# MCU098_01_MSPM0G3507_Target_Device.net
KiCad netlist of a schematic drawn in Altium Designer
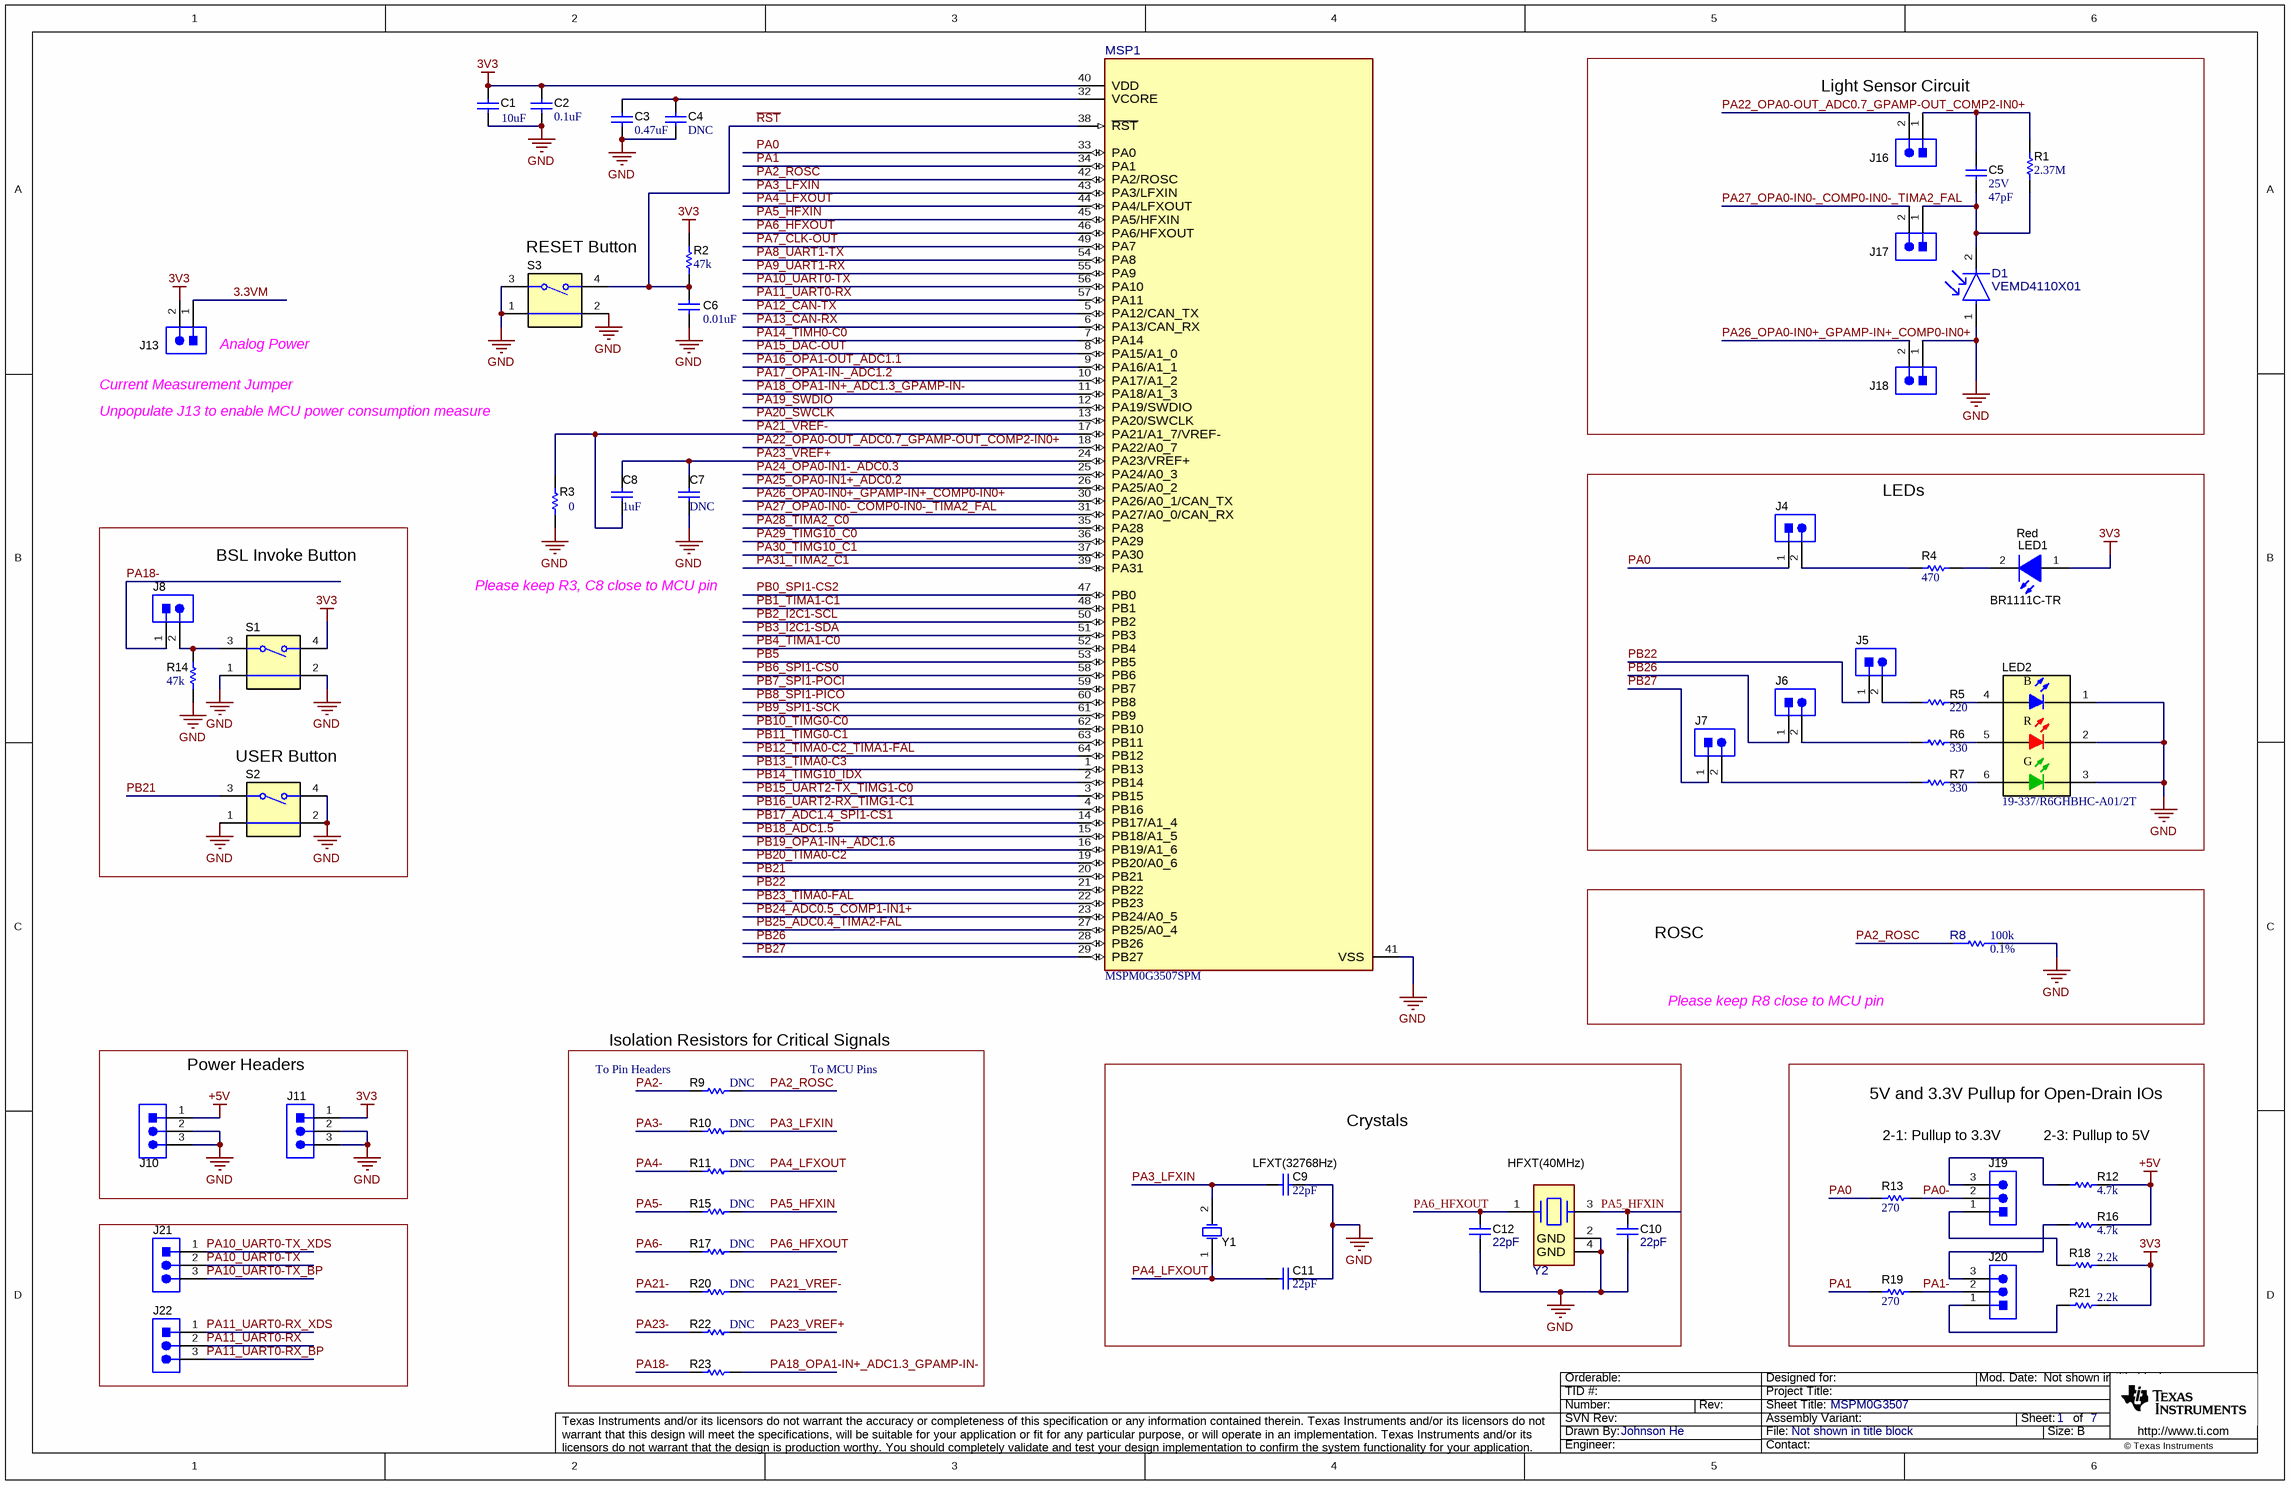
[diagram p0: MCU098_01_MSPM0G3507_Target_Device.SchDoc]

(export (version "E")
  (design (tool "Eeschema 10.0.6"))
  (components
    (comp (ref "C1")
      (value "GRM188R60J106ME84")
      (footprint "0603")
      (description "CAP, CERM, 10 uF, 6.3 V, +/- 20%, X5R, 0603")
      (fields
        (field (name "MANUFACTURER") "MuRata")
        (field (name "VALUEDISPLAYED") "10uF")
        (field (name "PUBLISHER") "Texas Instruments")
      )
      (libsource (lib "Altium Vault - TI") (part "Capacitor"))
    )
    (comp (ref "C2")
      (value "GRM155R61H104ME14D")
      (footprint "0402")
      (description "CAP, CERM, 0.1 uF, 50 V, +/- 20%, X5R, 0402")
      (fields
        (field (name "MANUFACTURER") "MuRata")
        (field (name "VALUEDISPLAYED") "0.1uF")
        (field (name "PUBLISHER") "Texas Instruments")
      )
      (libsource (lib "Altium Vault - TI") (part "Capacitor"))
    )
    (comp (ref "C3")
      (value "GRM155R60J474KE19D")
      (footprint "0402")
      (description "CAP, CERM, 0.47 uF, 6.3 V, +/- 10%, X5R, 0402")
      (fields
        (field (name "MANUFACTURER") "MuRata")
        (field (name "VALUEDISPLAYED") "0.47uF")
        (field (name "PUBLISHER") "Texas Instruments")
      )
      (libsource (lib "Altium Vault - TI") (part "Capacitor"))
    )
    (comp (ref "C4")
      (value "GRM155R61H104ME14D")
      (footprint "0402")
      (description "CAP, CERM, 0.1 uF, 50 V, +/- 20%, X5R, 0402")
      (fields
        (field (name "MANUFACTURER") "MuRata")
        (field (name "VALUEDISPLAYED") "DNC")
        (field (name "PUBLISHER") "Texas Instruments")
      )
      (libsource (lib "Altium Vault - TI") (part "Capacitor"))
    )
    (comp (ref "C5")
      (value "GRM1555C1E470JA01D")
      (footprint "0402")
      (description "CAP, CERM, 47 pF, 25 V, +/- 5%, C0G/NP0, 0402")
      (fields
        (field (name "MANUFACTURER") "MuRata")
        (field (name "VDC_V") "25V")
        (field (name "VALUEDISPLAYED") "47pF")
        (field (name "PUBLISHER") "Texas Instruments")
      )
      (libsource (lib "Altium Vault - TI") (part "Capacitor"))
    )
    (comp (ref "C6")
      (value "GRM155R61C103KA01D")
      (footprint "0402")
      (description "CAP, CERM, 0.01 uF, 16 V, +/- 10%, X5R, 0402")
      (fields
        (field (name "MANUFACTURER") "MuRata")
        (field (name "VALUEDISPLAYED") "0.01uF")
        (field (name "PUBLISHER") "Texas Instruments")
      )
      (libsource (lib "Altium Vault - TI") (part "Capacitor"))
    )
    (comp (ref "C7")
      (value "C1608X5R1E105K080AC")
      (footprint "0603")
      (description "CAP, CERM, 1 uF, 25 V, +/- 10%, X5R, 0603")
      (fields
        (field (name "MANUFACTURER") "TDK")
        (field (name "VALUEDISPLAYED") "DNC")
        (field (name "PUBLISHER") "Texas Instruments")
      )
      (libsource (lib "Altium Vault - TI") (part "Capacitor"))
    )
    (comp (ref "C8")
      (value "1uF")
      (footprint "0603")
      (description "CAP, CERM, 1 uF, 25 V, +/- 10%, X5R, 0603")
      (fields
        (field (name "MANUFACTURER") "TDK")
        (field (name "PARTNUMBER") "C1608X5R1E105K080AC")
        (field (name "PUBLISHER") "Texas Instruments")
      )
      (libsource (lib "Altium Vault - TI") (part "Capacitor"))
    )
    (comp (ref "C9")
      (value "GRM1555C1H220JA01D")
      (footprint "0402")
      (description "CAP, CERM, 22 pF, 50 V, +/- 5%, C0G/NP0, 0402")
      (fields
        (field (name "MANUFACTURER") "MuRata")
        (field (name "VALUEDISPLAYED") "22pF")
        (field (name "PUBLISHER") "Texas Instruments")
      )
      (libsource (lib "Altium Vault - TI") (part "Capacitor"))
    )
    (comp (ref "C10")
      (value "GRM1555C1H220JA01D")
      (footprint "0402")
      (description "CAP, CERM, 22 pF, 50 V, +/- 5%, C0G/NP0, 0402")
      (fields
        (field (name "MANUFACTURER") "MuRata")
        (field (name "VALUEDISPLAYED") "22pF")
        (field (name "PUBLISHER") "Texas Instruments")
      )
      (libsource (lib "Altium Vault - TI") (part "Capacitor"))
    )
    (comp (ref "C11")
      (value "GRM1555C1H220JA01D")
      (footprint "0402")
      (description "CAP, CERM, 22 pF, 50 V, +/- 5%, C0G/NP0, 0402")
      (fields
        (field (name "MANUFACTURER") "MuRata")
        (field (name "VALUEDISPLAYED") "22pF")
        (field (name "PUBLISHER") "Texas Instruments")
      )
      (libsource (lib "Altium Vault - TI") (part "Capacitor"))
    )
    (comp (ref "C12")
      (value "GRM1555C1H220JA01D")
      (footprint "0402")
      (description "CAP, CERM, 22 pF, 50 V, +/- 5%, C0G/NP0, 0402")
      (fields
        (field (name "MANUFACTURER") "MuRata")
        (field (name "VALUEDISPLAYED") "22pF")
        (field (name "PUBLISHER") "Texas Instruments")
      )
      (libsource (lib "Altium Vault - TI") (part "Capacitor"))
    )
    (comp (ref "D1")
      (value "VEMD4110X01")
      (footprint "FP-VEMD4110X01_0805-MFG")
      (description "Photodiode PIN Chip 910nm Automotive 2-Pin Case 0805(2012Metric) T/R")
      (fields
        (field (name "MANUFACTURER") "Vishay")
        (field (name "DIGIKEY PART NUMBER") "751-VEMD4110X01CT-ND")
      )
      (libsource (lib "Altium Vault - TI") (part "SYM-VEMD4110X01"))
    )
    (comp (ref "J4")
      (value "90120-0122")
      (footprint "CONN_90120-0122")
      (description "Header, 100mil, 2x1, Tin, TH")
      (fields (field (name "MANUFACTURER") "Molex") (field (name "PUBLISHER") "Texas Instruments"))
      (libsource (lib "") (part "Header_2x1_1"))
    )
    (comp (ref "J5")
      (value "90120-0122")
      (footprint "CONN_90120-0122")
      (description "Header, 100mil, 2x1, Tin, TH")
      (fields (field (name "MANUFACTURER") "Molex") (field (name "PUBLISHER") "Texas Instruments"))
      (libsource (lib "") (part "Header_2x1_1"))
    )
    (comp (ref "J6")
      (value "90120-0122")
      (footprint "CONN_90120-0122")
      (description "Header, 100mil, 2x1, Tin, TH")
      (fields (field (name "MANUFACTURER") "Molex") (field (name "PUBLISHER") "Texas Instruments"))
      (libsource (lib "") (part "Header_2x1_1"))
    )
    (comp (ref "J7")
      (value "90120-0122")
      (footprint "CONN_90120-0122")
      (description "Header, 100mil, 2x1, Tin, TH")
      (fields (field (name "MANUFACTURER") "Molex") (field (name "PUBLISHER") "Texas Instruments"))
      (libsource (lib "") (part "Header_2x1_1"))
    )
    (comp (ref "J8")
      (value "90120-0122")
      (footprint "CONN_90120-0122")
      (description "Header, 100mil, 2x1, Tin, TH")
      (fields (field (name "MANUFACTURER") "Molex") (field (name "PUBLISHER") "Texas Instruments"))
      (libsource (lib "") (part "Header_2x1_1"))
    )
    (comp (ref "J10")
      (value "PEC03SAAN")
      (footprint "PEC03SAAN_Launchpad_5V0")
      (description "Header, 100mil, 3x1, Tin, TH")
      (fields
        (field (name "MANUFACTURER") "Sullins Connector Solutions")
        (field (name "PUBLISHER") "Texas Instruments")
      )
      (libsource (lib "") (part "Header_3x1_Launchpad_1"))
    )
    (comp (ref "J11")
      (value "PEC03SAAN")
      (footprint "PEC03SAAN_Launchpad_3V3")
      (description "Header, 100mil, 3x1, Tin, TH")
      (fields
        (field (name "MANUFACTURER") "Sullins Connector Solutions")
        (field (name "PUBLISHER") "Texas Instruments")
      )
      (libsource (lib "") (part "Header_3x1_Launchpad_1"))
    )
    (comp (ref "J13")
      (value "90120-0122")
      (footprint "CONN_90120-0122")
      (description "Header, 100mil, 2x1, Tin, TH")
      (fields (field (name "MANUFACTURER") "Molex") (field (name "PUBLISHER") "Texas Instruments"))
      (libsource (lib "Altium Vault - TI") (part "Header_2x1"))
    )
    (comp (ref "J16")
      (value "90120-0122")
      (footprint "CONN_90120-0122")
      (description "Header, 100mil, 2x1, Tin, TH")
      (fields (field (name "MANUFACTURER") "Molex") (field (name "PUBLISHER") "Texas Instruments"))
      (libsource (lib "Altium Vault - TI") (part "Header_2x1"))
    )
    (comp (ref "J17")
      (value "90120-0122")
      (footprint "CONN_90120-0122")
      (description "Header, 100mil, 2x1, Tin, TH")
      (fields (field (name "MANUFACTURER") "Molex") (field (name "PUBLISHER") "Texas Instruments"))
      (libsource (lib "Altium Vault - TI") (part "Header_2x1"))
    )
    (comp (ref "J18")
      (value "90120-0122")
      (footprint "CONN_90120-0122")
      (description "Header, 100mil, 2x1, Tin, TH")
      (fields (field (name "MANUFACTURER") "Molex") (field (name "PUBLISHER") "Texas Instruments"))
      (libsource (lib "Altium Vault - TI") (part "Header_2x1"))
    )
    (comp (ref "J19")
      (value "PEC03SAAN")
      (footprint "CONN_PEC03SAAN")
      (description "Header, 100mil, 3x1, Tin, TH")
      (fields
        (field (name "MANUFACTURER") "Sullins Connector Solutions")
        (field (name "PUBLISHER") "Texas Instruments")
      )
      (libsource (lib "Altium Vault - TI") (part "Header_3x1_Launchpad"))
    )
    (comp (ref "J20")
      (value "PEC03SAAN")
      (footprint "CONN_PEC03SAAN")
      (description "Header, 100mil, 3x1, Tin, TH")
      (fields
        (field (name "MANUFACTURER") "Sullins Connector Solutions")
        (field (name "PUBLISHER") "Texas Instruments")
      )
      (libsource (lib "Altium Vault - TI") (part "Header_3x1_Launchpad"))
    )
    (comp (ref "J21")
      (value "PEC03SAAN")
      (footprint "CONN_PEC03SAAN")
      (description "Header, 100mil, 3x1, Tin, TH")
      (fields
        (field (name "MANUFACTURER") "Sullins Connector Solutions")
        (field (name "PUBLISHER") "Texas Instruments")
      )
      (libsource (lib "") (part "Header_3x1_Launchpad_1"))
    )
    (comp (ref "J22")
      (value "PEC03SAAN")
      (footprint "CONN_PEC03SAAN")
      (description "Header, 100mil, 3x1, Tin, TH")
      (fields
        (field (name "MANUFACTURER") "Sullins Connector Solutions")
        (field (name "PUBLISHER") "Texas Instruments")
      )
      (libsource (lib "") (part "Header_3x1_Launchpad_1"))
    )
    (comp (ref "LED1")
      (value "BR1111C-TR")
      (footprint "1111C_Red")
      (description "LED, Red, SMD")
      (fields (field (name "ALTIUM_VALUE") "Red") (field (name "MANUFACTURER") "Stanley Electric Co., LTD"))
      (libsource (lib "Altium Vault - TI") (part "LED"))
    )
    (comp (ref "LED2")
      (value "19-337/R6GHBHC-A01/2T")
      (footprint "19-337_RGB")
      (description "LED, RGB, SMD")
      (fields (field (name "MANUFACTURER") "Everlight") (field (name "PUBLISHER") "Texas Instruments"))
      (libsource (lib "Altium Vault - TI") (part "LED_RGB_A456K123"))
    )
    (comp (ref "MSP1")
      (value "MSPM0G3507SPM")
      (footprint "PM0064A-MFG")
      (description "Mixed-Signal Microcontrollers With CAN-FD Interface LQFP64")
      (fields (field (name "PARTNUMBER") "MSPM0G3507SPM") (field (name "MANUFACTURER") "Texas Instruments"))
      (libsource (lib "Altium Vault - TI") (part "SYM-MSPM0G3507SPM"))
    )
    (comp (ref "R1")
      (value "CRCW06032M37FKEA")
      (footprint "0603")
      (description "RES, 2.37 M, 1%, 0.1 W, 0603")
      (fields
        (field (name "MANUFACTURER") "Vishay-Dale")
        (field (name "VALUEDISPLAYED") "2.37M")
        (field (name "PUBLISHER") "Texas Instruments")
      )
      (libsource (lib "Altium Vault - TI") (part "Resistor"))
    )
    (comp (ref "R2")
      (value "CRCW040247K0JNED")
      (footprint "0402")
      (description "RES, 47 k, 5%, 0.063 W, 0402")
      (fields
        (field (name "MANUFACTURER") "Vishay-Dale")
        (field (name "VALUEDISPLAYED") "47k")
        (field (name "PUBLISHER") "Texas Instruments")
      )
      (libsource (lib "Altium Vault - TI") (part "Resistor"))
    )
    (comp (ref "R3")
      (value "0")
      (footprint "0603")
      (description "RES, 0, 5%, 0.1 W, 0603")
      (fields (field (name "MANUFACTURER") "Yageo") (field (name "PARTNUMBER") "RC0603JR-070RL"))
      (libsource (lib "Altium Vault - TI") (part "Resistor"))
    )
    (comp (ref "R4")
      (value "CRCW0402470RJNED")
      (footprint "0402")
      (description "RES, 470, 5%, 0.063 W, 0402")
      (fields
        (field (name "MANUFACTURER") "Vishay-Dale")
        (field (name "VALUEDISPLAYED") "470")
        (field (name "PUBLISHER") "Texas Instruments")
      )
      (libsource (lib "Altium Vault - TI") (part "Resistor"))
    )
    (comp (ref "R5")
      (value "CRCW0402220RJNED")
      (footprint "0402")
      (description "RES, 220, 5%, 0.063 W, 0402")
      (fields
        (field (name "MANUFACTURER") "Vishay-Dale")
        (field (name "VALUEDISPLAYED") "220")
        (field (name "PUBLISHER") "Texas Instruments")
      )
      (libsource (lib "Altium Vault - TI") (part "Resistor"))
    )
    (comp (ref "R6")
      (value "CRCW0402330RJNED")
      (footprint "0402")
      (description "RES, 330, 5%, 0.063 W, 0402")
      (fields
        (field (name "MANUFACTURER") "Vishay-Dale")
        (field (name "VALUEDISPLAYED") "330")
        (field (name "PUBLISHER") "Texas Instruments")
      )
      (libsource (lib "Altium Vault - TI") (part "Resistor"))
    )
    (comp (ref "R7")
      (value "CRCW0402330RJNED")
      (footprint "0402")
      (description "RES, 330, 5%, 0.063 W, 0402")
      (fields
        (field (name "MANUFACTURER") "Vishay-Dale")
        (field (name "VALUEDISPLAYED") "330")
        (field (name "PUBLISHER") "Texas Instruments")
      )
      (libsource (lib "Altium Vault - TI") (part "Resistor"))
    )
    (comp (ref "R8")
      (value "ERA-2AEB104X")
      (footprint "FP-ERA-2AEB104X_0402-MFG")
      (description "Res Thin Film 0402 100K Ohm 0.1% 1/16W ±25ppm/°C Molded SMD SMD Punched Carrier T/R")
      (fields
        (field (name "DIGIKEY PART NUMBER") "P100KDCCT-ND")
        (field (name "MANUFACTURER") "Panasonic")
        (field (name "TOLERANCE_%") "0.1%")
        (field (name "RES_OHM") "100k")
      )
      (libsource (lib "Altium Vault - TI") (part "SYM-ERA-2AEB104X"))
    )
    (comp (ref "R9")
      (value "RC0402JR-070RL")
      (footprint "0402")
      (description "RES, 0, 5%, 0.063 W, 0402")
      (fields
        (field (name "MANUFACTURER") "Yageo America")
        (field (name "VALUEDISPLAYED") "DNC")
        (field (name "PUBLISHER") "Texas Instruments")
      )
      (libsource (lib "Altium Vault - TI") (part "Resistor"))
    )
    (comp (ref "R10")
      (value "RC0402JR-070RL")
      (footprint "0402")
      (description "RES, 0, 5%, 0.063 W, 0402")
      (fields
        (field (name "MANUFACTURER") "Yageo America")
        (field (name "VALUEDISPLAYED") "DNC")
        (field (name "PUBLISHER") "Texas Instruments")
      )
      (libsource (lib "Altium Vault - TI") (part "Resistor"))
    )
    (comp (ref "R11")
      (value "RC0402JR-070RL")
      (footprint "0402")
      (description "RES, 0, 5%, 0.063 W, 0402")
      (fields
        (field (name "MANUFACTURER") "Yageo America")
        (field (name "VALUEDISPLAYED") "DNC")
        (field (name "PUBLISHER") "Texas Instruments")
      )
      (libsource (lib "Altium Vault - TI") (part "Resistor"))
    )
    (comp (ref "R12")
      (value "RC0603JR-074K7L")
      (footprint "0603")
      (description "RES, 4.7 k, 5%, 0.1 W, 0603")
      (fields (field (name "MANUFACTURER") "Yageo") (field (name "VALUEDISPLAYED") "4.7k"))
      (libsource (lib "Altium Vault - TI") (part "Resistor"))
    )
    (comp (ref "R13")
      (value "CRCW0402270RJNED")
      (footprint "0402")
      (description "RES, 270, 5%, 0.063 W, 0402")
      (fields
        (field (name "MANUFACTURER") "Vishay-Dale")
        (field (name "VALUEDISPLAYED") "270")
        (field (name "PUBLISHER") "Texas Instruments")
      )
      (libsource (lib "Altium Vault - TI") (part "Resistor"))
    )
    (comp (ref "R14")
      (value "CRCW040247K0JNED")
      (footprint "0402")
      (description "RES, 47 k, 5%, 0.063 W, 0402")
      (fields
        (field (name "MANUFACTURER") "Vishay-Dale")
        (field (name "VALUEDISPLAYED") "47k")
        (field (name "PUBLISHER") "Texas Instruments")
      )
      (libsource (lib "Altium Vault - TI") (part "Resistor"))
    )
    (comp (ref "R15")
      (value "RC0402JR-070RL")
      (footprint "0402")
      (description "RES, 0, 5%, 0.063 W, 0402")
      (fields
        (field (name "MANUFACTURER") "Yageo America")
        (field (name "VALUEDISPLAYED") "DNC")
        (field (name "PUBLISHER") "Texas Instruments")
      )
      (libsource (lib "Altium Vault - TI") (part "Resistor"))
    )
    (comp (ref "R16")
      (value "RC0603JR-074K7L")
      (footprint "0603")
      (description "RES, 4.7 k, 5%, 0.1 W, 0603")
      (fields (field (name "MANUFACTURER") "Yageo") (field (name "VALUEDISPLAYED") "4.7k"))
      (libsource (lib "Altium Vault - TI") (part "Resistor"))
    )
    (comp (ref "R17")
      (value "RC0402JR-070RL")
      (footprint "0402")
      (description "RES, 0, 5%, 0.063 W, 0402")
      (fields
        (field (name "MANUFACTURER") "Yageo America")
        (field (name "VALUEDISPLAYED") "DNC")
        (field (name "PUBLISHER") "Texas Instruments")
      )
      (libsource (lib "Altium Vault - TI") (part "Resistor"))
    )
    (comp (ref "R18")
      (value "RC0603JR-0710KL")
      (footprint "0603")
      (description "RES, 2.2 k, 5%, 0.1 W, 0603")
      (fields
        (field (name "PARTNUMBER") "RC0603JR-072K2L")
        (field (name "MANUFACTURER") "Yageo")
        (field (name "VALUEDISPLAYED") "2.2k")
      )
      (libsource (lib "Altium Vault - TI") (part "Resistor"))
    )
    (comp (ref "R19")
      (value "CRCW0402270RJNED")
      (footprint "0402")
      (description "RES, 270, 5%, 0.063 W, 0402")
      (fields
        (field (name "MANUFACTURER") "Vishay-Dale")
        (field (name "VALUEDISPLAYED") "270")
        (field (name "PUBLISHER") "Texas Instruments")
      )
      (libsource (lib "Altium Vault - TI") (part "Resistor"))
    )
    (comp (ref "R20")
      (value "RC0402JR-070RL")
      (footprint "0402")
      (description "RES, 0, 5%, 0.063 W, 0402")
      (fields
        (field (name "MANUFACTURER") "Yageo America")
        (field (name "VALUEDISPLAYED") "DNC")
        (field (name "PUBLISHER") "Texas Instruments")
      )
      (libsource (lib "Altium Vault - TI") (part "Resistor"))
    )
    (comp (ref "R21")
      (value "RC0603JR-0710KL")
      (footprint "0603")
      (description "RES, 2.2 k, 5%, 0.1 W, 0603")
      (fields
        (field (name "PARTNUMBER") "RC0603JR-072K2L")
        (field (name "MANUFACTURER") "Yageo")
        (field (name "VALUEDISPLAYED") "2.2k")
      )
      (libsource (lib "Altium Vault - TI") (part "Resistor"))
    )
    (comp (ref "R22")
      (value "RC0402JR-070RL")
      (footprint "0402")
      (description "RES, 0, 5%, 0.063 W, 0402")
      (fields
        (field (name "MANUFACTURER") "Yageo America")
        (field (name "VALUEDISPLAYED") "DNC")
        (field (name "PUBLISHER") "Texas Instruments")
      )
      (libsource (lib "Altium Vault - TI") (part "Resistor"))
    )
    (comp (ref "R23")
      (value "RC0402JR-070RL")
      (footprint "0402")
      (description "RES, 0, 5%, 0.063 W, 0402")
      (fields (field (name "MANUFACTURER") "Yageo America") (field (name "PUBLISHER") "Texas Instruments"))
      (libsource (lib "Altium Vault - TI") (part "Resistor"))
    )
    (comp (ref "S1")
      (value "1188E-1K2-V-TR")
      (footprint "SW_1188E")
      (description "Switch, SPST, 0.05 A, 12 VDC, SMD")
      (fields (field (name "MANUFACTURER") "Diptronics") (field (name "PUBLISHER") "Texas Instruments"))
      (libsource (lib "Altium Vault - TI") (part "SW_1188E"))
    )
    (comp (ref "S2")
      (value "1188E-1K2-V-TR")
      (footprint "SW_1188E")
      (description "Switch, SPST, 0.05 A, 12 VDC, SMD")
      (fields (field (name "MANUFACTURER") "Diptronics") (field (name "PUBLISHER") "Texas Instruments"))
      (libsource (lib "Altium Vault - TI") (part "SW_1188E"))
    )
    (comp (ref "S3")
      (value "1188E-1K2-V-TR")
      (footprint "SW_1188E")
      (description "Switch, SPST, 0.05 A, 12 VDC, SMD")
      (fields (field (name "MANUFACTURER") "Diptronics") (field (name "PUBLISHER") "Texas Instruments"))
      (libsource (lib "Altium Vault - TI") (part "SW_1188E"))
    )
    (comp (ref "Y1")
      (value "X1A0001410014")
      (footprint "Epson_FC-135")
      (description "Crystal, 32.768 KHz, 12.5 pF, SMD")
      (fields (field (name "MANUFACTURER") "Epson") (field (name "PUBLISHER") "Texas Instruments"))
      (libsource (lib "Altium Vault - TI") (part "Xtal"))
    )
    (comp (ref "Y2")
      (value "X1E0000210179")
      (footprint "FP-X1E0000210179_TSX-3225-MFG")
      (description "Crystal 40MHz ±10ppm (Tol) ±20ppm (Stability) 12pF FUND 40Ohm 4-Pin Mini-CSMD T/R")
      (fields (field (name "MANUFACTURER") "Seiko Epson"))
      (libsource (lib "Altium Vault - TI") (part "SYM-X1E0000210179"))
    )
  )
  (nets
    (net (code "1") (name "+5V") (class "Default")
      (node (ref "J10") (pin "1") (pinfunction "1_1") (pintype "passive"))
      (node (ref "R12") (pin "2") (pinfunction "2_2") (pintype "passive"))
      (node (ref "R16") (pin "2") (pinfunction "2_2") (pintype "passive"))
    )
    (net (code "2") (name "/3.3VM") (class "Default")
      (node (ref "J13") (pin "1") (pinfunction "1_1") (pintype "passive"))
    )
    (net (code "3") (name "/PA0") (class "Default")
      (node (ref "J4") (pin "1") (pinfunction "1_1") (pintype "passive"))
      (node (ref "MSP1") (pin "33") (pinfunction "PA0_33") (pintype "bidirectional"))
      (node (ref "R13") (pin "1") (pinfunction "1_1") (pintype "passive"))
    )
    (net (code "4") (name "/PA0-") (class "Default")
      (node (ref "J19") (pin "2") (pinfunction "2_2") (pintype "passive"))
      (node (ref "R13") (pin "2") (pinfunction "2_2") (pintype "passive"))
    )
    (net (code "5") (name "/PA1") (class "Default")
      (node (ref "MSP1") (pin "34") (pinfunction "PA1_34") (pintype "bidirectional"))
      (node (ref "R19") (pin "1") (pinfunction "1_1") (pintype "passive"))
    )
    (net (code "6") (name "/PA1-") (class "Default")
      (node (ref "J20") (pin "2") (pinfunction "2_2") (pintype "passive"))
      (node (ref "R19") (pin "2") (pinfunction "2_2") (pintype "passive"))
    )
    (net (code "7") (name "/PA2-") (class "Default")
      (node (ref "R9") (pin "1") (pinfunction "1_1") (pintype "passive"))
    )
    (net (code "8") (name "/PA2_ROSC") (class "Default")
      (node (ref "MSP1") (pin "42") (pinfunction "PA2/ROSC_42") (pintype "bidirectional"))
      (node (ref "R8") (pin "1") (pinfunction "1_1") (pintype "passive"))
      (node (ref "R9") (pin "2") (pinfunction "2_2") (pintype "passive"))
    )
    (net (code "9") (name "/PA3-") (class "Default")
      (node (ref "R10") (pin "1") (pinfunction "1_1") (pintype "passive"))
    )
    (net (code "10") (name "/PA3_LFXIN") (class "Default")
      (node (ref "C9") (pin "2") (pinfunction "2_2") (pintype "passive"))
      (node (ref "MSP1") (pin "43") (pinfunction "PA3/LFXIN_43") (pintype "bidirectional"))
      (node (ref "R10") (pin "2") (pinfunction "2_2") (pintype "passive"))
      (node (ref "Y1") (pin "2") (pinfunction "OSC2_2") (pintype "passive"))
    )
    (net (code "11") (name "/PA4-") (class "Default")
      (node (ref "R11") (pin "1") (pinfunction "1_1") (pintype "passive"))
    )
    (net (code "12") (name "/PA4_LFXOUT") (class "Default")
      (node (ref "C11") (pin "2") (pinfunction "2_2") (pintype "passive"))
      (node (ref "MSP1") (pin "44") (pinfunction "PA4/LFXOUT_44") (pintype "bidirectional"))
      (node (ref "R11") (pin "2") (pinfunction "2_2") (pintype "passive"))
      (node (ref "Y1") (pin "1") (pinfunction "OSC1_1") (pintype "passive"))
    )
    (net (code "13") (name "/PA5-") (class "Default")
      (node (ref "R15") (pin "1") (pinfunction "1_1") (pintype "passive"))
    )
    (net (code "14") (name "/PA5_HFXIN") (class "Default")
      (node (ref "C10") (pin "2") (pinfunction "2_2") (pintype "passive"))
      (node (ref "MSP1") (pin "45") (pinfunction "PA5/HFXIN_45") (pintype "bidirectional"))
      (node (ref "R15") (pin "2") (pinfunction "2_2") (pintype "passive"))
      (node (ref "Y2") (pin "3") (pinfunction "3_3") (pintype "passive"))
    )
    (net (code "15") (name "/PA6-") (class "Default")
      (node (ref "R17") (pin "1") (pinfunction "1_1") (pintype "passive"))
    )
    (net (code "16") (name "/PA6_HFXOUT") (class "Default")
      (node (ref "C12") (pin "2") (pinfunction "2_2") (pintype "passive"))
      (node (ref "MSP1") (pin "46") (pinfunction "PA6/HFXOUT_46") (pintype "bidirectional"))
      (node (ref "R17") (pin "2") (pinfunction "2_2") (pintype "passive"))
      (node (ref "Y2") (pin "1") (pinfunction "1_1") (pintype "passive"))
    )
    (net (code "17") (name "/PA7_CLK-OUT") (class "Default")
      (node (ref "MSP1") (pin "49") (pinfunction "PA7_49") (pintype "bidirectional"))
    )
    (net (code "18") (name "/PA8_UART1-TX") (class "Default")
      (node (ref "MSP1") (pin "54") (pinfunction "PA8_54") (pintype "bidirectional"))
    )
    (net (code "19") (name "/PA9_UART1-RX") (class "Default")
      (node (ref "MSP1") (pin "55") (pinfunction "PA9_55") (pintype "bidirectional"))
    )
    (net (code "20") (name "/PA10_UART0-TX") (class "Default")
      (node (ref "J21") (pin "2") (pinfunction "2_2") (pintype "passive"))
      (node (ref "MSP1") (pin "56") (pinfunction "PA10_56") (pintype "bidirectional"))
    )
    (net (code "21") (name "/PA10_UART0-TX_BP") (class "Default")
      (node (ref "J21") (pin "3") (pinfunction "3_3") (pintype "passive"))
    )
    (net (code "22") (name "/PA10_UART0-TX_XDS") (class "Default")
      (node (ref "J21") (pin "1") (pinfunction "1_1") (pintype "passive"))
    )
    (net (code "23") (name "/PA11_UART0-RX") (class "Default")
      (node (ref "J22") (pin "2") (pinfunction "2_2") (pintype "passive"))
      (node (ref "MSP1") (pin "57") (pinfunction "PA11_57") (pintype "bidirectional"))
    )
    (net (code "24") (name "/PA11_UART0-RX_BP") (class "Default")
      (node (ref "J22") (pin "3") (pinfunction "3_3") (pintype "passive"))
    )
    (net (code "25") (name "/PA11_UART0-RX_XDS") (class "Default")
      (node (ref "J22") (pin "1") (pinfunction "1_1") (pintype "passive"))
    )
    (net (code "26") (name "/PA12_CAN-TX") (class "Default")
      (node (ref "MSP1") (pin "5") (pinfunction "PA12/CAN_TX_5") (pintype "bidirectional"))
    )
    (net (code "27") (name "/PA13_CAN-RX") (class "Default")
      (node (ref "MSP1") (pin "6") (pinfunction "PA13/CAN_RX_6") (pintype "bidirectional"))
    )
    (net (code "28") (name "/PA14_TIMH0-C0") (class "Default")
      (node (ref "MSP1") (pin "7") (pinfunction "PA14_7") (pintype "bidirectional"))
    )
    (net (code "29") (name "/PA15_DAC-OUT") (class "Default")
      (node (ref "MSP1") (pin "8") (pinfunction "PA15/A1_0_8") (pintype "bidirectional"))
    )
    (net (code "30") (name "/PA16_OPA1-OUT_ADC1.1") (class "Default")
      (node (ref "MSP1") (pin "9") (pinfunction "PA16/A1_1_9") (pintype "bidirectional"))
    )
    (net (code "31") (name "/PA17_OPA1-IN-_ADC1.2") (class "Default")
      (node (ref "MSP1") (pin "10") (pinfunction "PA17/A1_2_10") (pintype "bidirectional"))
    )
    (net (code "32") (name "/PA18-") (class "Default")
      (node (ref "J8") (pin "1") (pinfunction "1_1") (pintype "passive"))
      (node (ref "R23") (pin "1") (pinfunction "1_1") (pintype "passive"))
    )
    (net (code "33") (name "/PA18_OPA1-IN+_ADC1.3_GPAMP-IN-") (class "Default")
      (node (ref "MSP1") (pin "11") (pinfunction "PA18/A1_3_11") (pintype "bidirectional"))
      (node (ref "R23") (pin "2") (pinfunction "2_2") (pintype "passive"))
    )
    (net (code "34") (name "/PA19_SWDIO") (class "Default")
      (node (ref "MSP1") (pin "12") (pinfunction "PA19/SWDIO_12") (pintype "bidirectional"))
    )
    (net (code "35") (name "/PA20_SWCLK") (class "Default")
      (node (ref "MSP1") (pin "13") (pinfunction "PA20/SWCLK_13") (pintype "bidirectional"))
    )
    (net (code "36") (name "/PA21-") (class "Default")
      (node (ref "R20") (pin "1") (pinfunction "1_1") (pintype "passive"))
    )
    (net (code "37") (name "/PA21_VREF-") (class "Default")
      (node (ref "C8") (pin "2") (pinfunction "2_2") (pintype "passive"))
      (node (ref "MSP1") (pin "17") (pinfunction "PA21/A1_7/VREF-_17") (pintype "bidirectional"))
      (node (ref "R20") (pin "2") (pinfunction "2_2") (pintype "passive"))
      (node (ref "R3") (pin "2") (pinfunction "2_2") (pintype "passive"))
    )
    (net (code "38") (name "/PA22_OPA0-OUT_ADC0.7_GPAMP-OUT_COMP2-IN0+") (class "Default")
      (node (ref "J16") (pin "2") (pinfunction "2_2") (pintype "passive"))
      (node (ref "MSP1") (pin "18") (pinfunction "PA22/A0_7_18") (pintype "bidirectional"))
    )
    (net (code "39") (name "/PA23-") (class "Default")
      (node (ref "R22") (pin "1") (pinfunction "1_1") (pintype "passive"))
    )
    (net (code "40") (name "/PA23_VREF+") (class "Default")
      (node (ref "C7") (pin "1") (pinfunction "1_1") (pintype "passive"))
      (node (ref "C8") (pin "1") (pinfunction "1_1") (pintype "passive"))
      (node (ref "MSP1") (pin "24") (pinfunction "PA23/VREF+_24") (pintype "bidirectional"))
      (node (ref "R22") (pin "2") (pinfunction "2_2") (pintype "passive"))
    )
    (net (code "41") (name "/PA24_OPA0-IN1-_ADC0.3") (class "Default")
      (node (ref "MSP1") (pin "25") (pinfunction "PA24/A0_3_25") (pintype "bidirectional"))
    )
    (net (code "42") (name "/PA25_OPA0-IN1+_ADC0.2") (class "Default")
      (node (ref "MSP1") (pin "26") (pinfunction "PA25/A0_2_26") (pintype "bidirectional"))
    )
    (net (code "43") (name "/PA26_OPA0-IN0+_GPAMP-IN+_COMP0-IN0+") (class "Default")
      (node (ref "J18") (pin "2") (pinfunction "2_2") (pintype "passive"))
      (node (ref "MSP1") (pin "30") (pinfunction "PA26/A0_1/CAN_TX_30") (pintype "bidirectional"))
    )
    (net (code "44") (name "/PA27_OPA0-IN0-_COMP0-IN0-_TIMA2_FAL") (class "Default")
      (node (ref "J17") (pin "2") (pinfunction "2_2") (pintype "passive"))
      (node (ref "MSP1") (pin "31") (pinfunction "PA27/A0_0/CAN_RX_31") (pintype "bidirectional"))
    )
    (net (code "45") (name "/PA28_TIMA2_C0") (class "Default")
      (node (ref "MSP1") (pin "35") (pinfunction "PA28_35") (pintype "bidirectional"))
    )
    (net (code "46") (name "/PA29_TIMG10_C0") (class "Default")
      (node (ref "MSP1") (pin "36") (pinfunction "PA29_36") (pintype "bidirectional"))
    )
    (net (code "47") (name "/PA30_TIMG10_C1") (class "Default")
      (node (ref "MSP1") (pin "37") (pinfunction "PA30_37") (pintype "bidirectional"))
    )
    (net (code "48") (name "/PA31_TIMA2_C1") (class "Default")
      (node (ref "MSP1") (pin "39") (pinfunction "PA31_39") (pintype "bidirectional"))
    )
    (net (code "49") (name "/PB0_SPI1-CS2") (class "Default")
      (node (ref "MSP1") (pin "47") (pinfunction "PB0_47") (pintype "bidirectional"))
    )
    (net (code "50") (name "/PB1_TIMA1-C1") (class "Default")
      (node (ref "MSP1") (pin "48") (pinfunction "PB1_48") (pintype "bidirectional"))
    )
    (net (code "51") (name "/PB2_I2C1-SCL") (class "Default")
      (node (ref "MSP1") (pin "50") (pinfunction "PB2_50") (pintype "bidirectional"))
    )
    (net (code "52") (name "/PB3_I2C1-SDA") (class "Default")
      (node (ref "MSP1") (pin "51") (pinfunction "PB3_51") (pintype "bidirectional"))
    )
    (net (code "53") (name "/PB4_TIMA1-C0") (class "Default")
      (node (ref "MSP1") (pin "52") (pinfunction "PB4_52") (pintype "bidirectional"))
    )
    (net (code "54") (name "/PB5") (class "Default")
      (node (ref "MSP1") (pin "53") (pinfunction "PB5_53") (pintype "bidirectional"))
    )
    (net (code "55") (name "/PB6_SPI1-CS0") (class "Default")
      (node (ref "MSP1") (pin "58") (pinfunction "PB6_58") (pintype "bidirectional"))
    )
    (net (code "56") (name "/PB7_SPI1-POCI") (class "Default")
      (node (ref "MSP1") (pin "59") (pinfunction "PB7_59") (pintype "bidirectional"))
    )
    (net (code "57") (name "/PB8_SPI1-PICO") (class "Default")
      (node (ref "MSP1") (pin "60") (pinfunction "PB8_60") (pintype "bidirectional"))
    )
    (net (code "58") (name "/PB9_SPI1-SCK") (class "Default")
      (node (ref "MSP1") (pin "61") (pinfunction "PB9_61") (pintype "bidirectional"))
    )
    (net (code "59") (name "/PB10_TIMG0-C0") (class "Default")
      (node (ref "MSP1") (pin "62") (pinfunction "PB10_62") (pintype "bidirectional"))
    )
    (net (code "60") (name "/PB11_TIMG0-C1") (class "Default")
      (node (ref "MSP1") (pin "63") (pinfunction "PB11_63") (pintype "bidirectional"))
    )
    (net (code "61") (name "/PB12_TIMA0-C2_TIMA1-FAL") (class "Default")
      (node (ref "MSP1") (pin "64") (pinfunction "PB12_64") (pintype "bidirectional"))
    )
    (net (code "62") (name "/PB13_TIMA0-C3") (class "Default")
      (node (ref "MSP1") (pin "1") (pinfunction "PB13_1") (pintype "bidirectional"))
    )
    (net (code "63") (name "/PB14_TIMG10_IDX") (class "Default")
      (node (ref "MSP1") (pin "2") (pinfunction "PB14_2") (pintype "bidirectional"))
    )
    (net (code "64") (name "/PB15_UART2-TX_TIMG1-C0") (class "Default")
      (node (ref "MSP1") (pin "3") (pinfunction "PB15_3") (pintype "bidirectional"))
    )
    (net (code "65") (name "/PB16_UART2-RX_TIMG1-C1") (class "Default")
      (node (ref "MSP1") (pin "4") (pinfunction "PB16_4") (pintype "bidirectional"))
    )
    (net (code "66") (name "/PB17_ADC1.4_SPI1-CS1") (class "Default")
      (node (ref "MSP1") (pin "14") (pinfunction "PB17/A1_4_14") (pintype "bidirectional"))
    )
    (net (code "67") (name "/PB18_ADC1.5") (class "Default")
      (node (ref "MSP1") (pin "15") (pinfunction "PB18/A1_5_15") (pintype "bidirectional"))
    )
    (net (code "68") (name "/PB19_OPA1-IN+_ADC1.6") (class "Default")
      (node (ref "MSP1") (pin "16") (pinfunction "PB19/A1_6_16") (pintype "bidirectional"))
    )
    (net (code "69") (name "/PB20_TIMA0-C2") (class "Default")
      (node (ref "MSP1") (pin "19") (pinfunction "PB20/A0_6_19") (pintype "bidirectional"))
    )
    (net (code "70") (name "/PB21") (class "Default")
      (node (ref "MSP1") (pin "20") (pinfunction "PB21_20") (pintype "bidirectional"))
      (node (ref "S2") (pin "3") (pinfunction "3_3") (pintype "passive"))
    )
    (net (code "71") (name "/PB22") (class "Default")
      (node (ref "J5") (pin "1") (pinfunction "1_1") (pintype "passive"))
      (node (ref "MSP1") (pin "21") (pinfunction "PB22_21") (pintype "bidirectional"))
    )
    (net (code "72") (name "/PB23_TIMA0-FAL") (class "Default")
      (node (ref "MSP1") (pin "22") (pinfunction "PB23_22") (pintype "bidirectional"))
    )
    (net (code "73") (name "/PB24_ADC0.5_COMP1-IN1+") (class "Default")
      (node (ref "MSP1") (pin "23") (pinfunction "PB24/A0_5_23") (pintype "bidirectional"))
    )
    (net (code "74") (name "/PB25_ADC0.4_TIMA2-FAL") (class "Default")
      (node (ref "MSP1") (pin "27") (pinfunction "PB25/A0_4_27") (pintype "bidirectional"))
    )
    (net (code "75") (name "/PB26") (class "Default")
      (node (ref "J6") (pin "1") (pinfunction "1_1") (pintype "passive"))
      (node (ref "MSP1") (pin "28") (pinfunction "PB26_28") (pintype "bidirectional"))
    )
    (net (code "76") (name "/PB27") (class "Default")
      (node (ref "J7") (pin "1") (pinfunction "1_1") (pintype "passive"))
      (node (ref "MSP1") (pin "29") (pinfunction "PB27_29") (pintype "bidirectional"))
    )
    (net (code "77") (name "/~{RST}") (class "Default")
      (node (ref "C6") (pin "1") (pinfunction "1_1") (pintype "passive"))
      (node (ref "MSP1") (pin "38") (pinfunction "~{RST}_38") (pintype "input"))
      (node (ref "R2") (pin "1") (pinfunction "1_1") (pintype "passive"))
      (node (ref "S3") (pin "4") (pinfunction "4_4") (pintype "passive"))
    )
    (net (code "78") (name "3V3") (class "Default")
      (node (ref "C1") (pin "1") (pinfunction "1_1") (pintype "passive"))
      (node (ref "C2") (pin "1") (pinfunction "1_1") (pintype "passive"))
      (node (ref "J11") (pin "1") (pinfunction "1_1") (pintype "passive"))
      (node (ref "J13") (pin "2") (pinfunction "2_2") (pintype "passive"))
      (node (ref "LED1") (pin "1") (pinfunction "A_1") (pintype "passive"))
      (node (ref "MSP1") (pin "40") (pinfunction "VDD_40") (pintype "power_in"))
      (node (ref "R18") (pin "2") (pinfunction "2_2") (pintype "passive"))
      (node (ref "R2") (pin "2") (pinfunction "2_2") (pintype "passive"))
      (node (ref "R21") (pin "2") (pinfunction "2_2") (pintype "passive"))
      (node (ref "S1") (pin "4") (pinfunction "4_4") (pintype "passive"))
    )
    (net (code "79") (name "GND") (class "Default")
      (node (ref "C1") (pin "2") (pinfunction "2_2") (pintype "passive"))
      (node (ref "C10") (pin "1") (pinfunction "1_1") (pintype "passive"))
      (node (ref "C11") (pin "1") (pinfunction "1_1") (pintype "passive"))
      (node (ref "C12") (pin "1") (pinfunction "1_1") (pintype "passive"))
      (node (ref "C2") (pin "2") (pinfunction "2_2") (pintype "passive"))
      (node (ref "C3") (pin "2") (pinfunction "2_2") (pintype "passive"))
      (node (ref "C4") (pin "2") (pinfunction "2_2") (pintype "passive"))
      (node (ref "C6") (pin "2") (pinfunction "2_2") (pintype "passive"))
      (node (ref "C7") (pin "2") (pinfunction "2_2") (pintype "passive"))
      (node (ref "C9") (pin "1") (pinfunction "1_1") (pintype "passive"))
      (node (ref "D1") (pin "1") (pinfunction "ANODE_1") (pintype "passive"))
      (node (ref "J10") (pin "2") (pinfunction "2_2") (pintype "passive"))
      (node (ref "J10") (pin "3") (pinfunction "3_3") (pintype "passive"))
      (node (ref "J11") (pin "2") (pinfunction "2_2") (pintype "passive"))
      (node (ref "J11") (pin "3") (pinfunction "3_3") (pintype "passive"))
      (node (ref "J18") (pin "1") (pinfunction "1_1") (pintype "passive"))
      (node (ref "LED2") (pin "1") (pinfunction "K_1") (pintype "passive"))
      (node (ref "LED2") (pin "2") (pinfunction "K_2") (pintype "passive"))
      (node (ref "LED2") (pin "3") (pinfunction "K_3") (pintype "passive"))
      (node (ref "MSP1") (pin "41") (pinfunction "VSS_41") (pintype "power_in"))
      (node (ref "R14") (pin "1") (pinfunction "1_1") (pintype "passive"))
      (node (ref "R3") (pin "1") (pinfunction "1_1") (pintype "passive"))
      (node (ref "R8") (pin "2") (pinfunction "2_2") (pintype "passive"))
      (node (ref "S1") (pin "1") (pinfunction "1_1") (pintype "passive"))
      (node (ref "S1") (pin "2") (pinfunction "2_2") (pintype "passive"))
      (node (ref "S2") (pin "1") (pinfunction "1_1") (pintype "passive"))
      (node (ref "S2") (pin "2") (pinfunction "2_2") (pintype "passive"))
      (node (ref "S2") (pin "4") (pinfunction "4_4") (pintype "passive"))
      (node (ref "S3") (pin "1") (pinfunction "1_1") (pintype "passive"))
      (node (ref "S3") (pin "2") (pinfunction "2_2") (pintype "passive"))
      (node (ref "S3") (pin "3") (pinfunction "3_3") (pintype "passive"))
      (node (ref "Y2") (pin "2") (pinfunction "GND_2") (pintype "power_in"))
      (node (ref "Y2") (pin "4") (pinfunction "GND_4") (pintype "power_in"))
    )
    (net (code "80") (name "Net-(C5-Pad1)") (class "Default")
      (node (ref "C5") (pin "1") (pinfunction "1_1") (pintype "passive"))
      (node (ref "J16") (pin "1") (pinfunction "1_1") (pintype "passive"))
      (node (ref "R1") (pin "2") (pinfunction "2_2") (pintype "passive"))
    )
    (net (code "81") (name "Net-(D1-CATHODE)") (class "Default")
      (node (ref "C5") (pin "2") (pinfunction "2_2") (pintype "passive"))
      (node (ref "D1") (pin "2") (pinfunction "CATHODE_2") (pintype "passive"))
      (node (ref "J17") (pin "1") (pinfunction "1_1") (pintype "passive"))
      (node (ref "R1") (pin "1") (pinfunction "1_1") (pintype "passive"))
    )
    (net (code "82") (name "Net-(J4-Pad2)") (class "Default")
      (node (ref "J4") (pin "2") (pinfunction "2_2") (pintype "passive"))
      (node (ref "R4") (pin "1") (pinfunction "1_1") (pintype "passive"))
    )
    (net (code "83") (name "Net-(J5-Pad2)") (class "Default")
      (node (ref "J5") (pin "2") (pinfunction "2_2") (pintype "passive"))
      (node (ref "R5") (pin "1") (pinfunction "1_1") (pintype "passive"))
    )
    (net (code "84") (name "Net-(J6-Pad2)") (class "Default")
      (node (ref "J6") (pin "2") (pinfunction "2_2") (pintype "passive"))
      (node (ref "R6") (pin "1") (pinfunction "1_1") (pintype "passive"))
    )
    (net (code "85") (name "Net-(J7-Pad2)") (class "Default")
      (node (ref "J7") (pin "2") (pinfunction "2_2") (pintype "passive"))
      (node (ref "R7") (pin "1") (pinfunction "1_1") (pintype "passive"))
    )
    (net (code "86") (name "Net-(J8-Pad2)") (class "Default")
      (node (ref "J8") (pin "2") (pinfunction "2_2") (pintype "passive"))
      (node (ref "R14") (pin "2") (pinfunction "2_2") (pintype "passive"))
      (node (ref "S1") (pin "3") (pinfunction "3_3") (pintype "passive"))
    )
    (net (code "87") (name "Net-(J19-Pad1)") (class "Default")
      (node (ref "J19") (pin "1") (pinfunction "1_1") (pintype "passive"))
      (node (ref "R18") (pin "1") (pinfunction "1_1") (pintype "passive"))
    )
    (net (code "88") (name "Net-(J19-Pad3)") (class "Default")
      (node (ref "J19") (pin "3") (pinfunction "3_3") (pintype "passive"))
      (node (ref "R12") (pin "1") (pinfunction "1_1") (pintype "passive"))
    )
    (net (code "89") (name "Net-(J20-Pad1)") (class "Default")
      (node (ref "J20") (pin "1") (pinfunction "1_1") (pintype "passive"))
      (node (ref "R21") (pin "1") (pinfunction "1_1") (pintype "passive"))
    )
    (net (code "90") (name "Net-(J20-Pad3)") (class "Default")
      (node (ref "J20") (pin "3") (pinfunction "3_3") (pintype "passive"))
      (node (ref "R16") (pin "1") (pinfunction "1_1") (pintype "passive"))
    )
    (net (code "91") (name "Net-(LED1-K)") (class "Default")
      (node (ref "LED1") (pin "2") (pinfunction "K_2") (pintype "passive"))
      (node (ref "R4") (pin "2") (pinfunction "2_2") (pintype "passive"))
    )
    (net (code "92") (name "Net-(LED2-A-Pad4)") (class "Default")
      (node (ref "LED2") (pin "4") (pinfunction "A_4") (pintype "passive"))
      (node (ref "R5") (pin "2") (pinfunction "2_2") (pintype "passive"))
    )
    (net (code "93") (name "Net-(LED2-A-Pad5)") (class "Default")
      (node (ref "LED2") (pin "5") (pinfunction "A_5") (pintype "passive"))
      (node (ref "R6") (pin "2") (pinfunction "2_2") (pintype "passive"))
    )
    (net (code "94") (name "Net-(LED2-A-Pad6)") (class "Default")
      (node (ref "LED2") (pin "6") (pinfunction "A_6") (pintype "passive"))
      (node (ref "R7") (pin "2") (pinfunction "2_2") (pintype "passive"))
    )
    (net (code "95") (name "Net-(MSP1-VCORE)") (class "Default")
      (node (ref "C3") (pin "1") (pinfunction "1_1") (pintype "passive"))
      (node (ref "C4") (pin "1") (pinfunction "1_1") (pintype "passive"))
      (node (ref "MSP1") (pin "32") (pinfunction "VCORE_32") (pintype "power_in"))
    )
  )
)
